# ESP-12S.net
KiCad netlist of a schematic drawn in Altium Designer
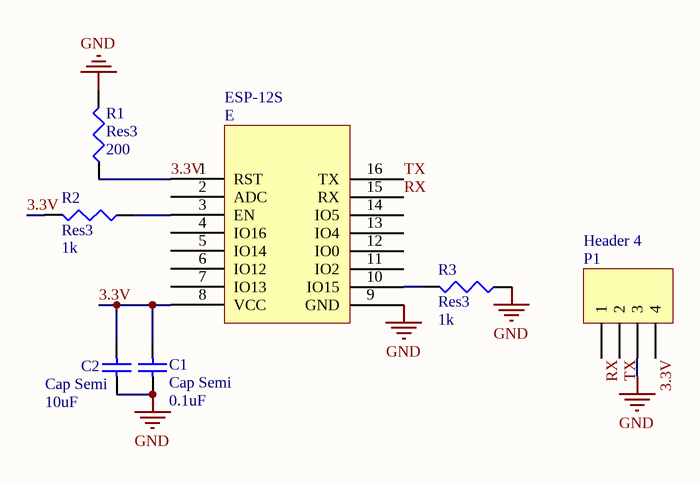
[diagram p0: ESP-12S.SchDoc]

(export (version "E")
  (design (tool "Eeschema 10.0.6"))
  (components
    (comp (ref "C1")
      (value "Cap Semi")
      (footprint "1608[0603]")
      (description "Capacitor (Semiconductor SIM Model)")
      (fields (field (name "ALTIUM_VALUE") "0.1uF") (field (name "PUBLISHER") "Altium Limited"))
      (libsource (lib "Miscellaneous Devices") (part "Cap Semi"))
    )
    (comp (ref "C2")
      (value "Cap Semi")
      (footprint "C2512")
      (description "Capacitor (Semiconductor SIM Model)")
      (fields (field (name "ALTIUM_VALUE") "10uF") (field (name "PUBLISHER") "Altium Limited"))
      (libsource (lib "Miscellaneous Devices") (part "Cap Semi"))
    )
    (comp (ref "E") (value "ESP-12S") (footprint "ESP-12S") (libsource (lib "ESP-12S") (part "ESP-12S")))
    (comp (ref "P1")
      (value "Header 4")
      (footprint "HDR1X4")
      (description "Header, 4-Pin")
      (fields (field (name "PUBLISHER") "Altium Limited"))
      (libsource (lib "Miscellaneous Connectors") (part "Header 4"))
    )
    (comp (ref "R1")
      (value "Res3")
      (footprint "J1-0603")
      (description "Resistor")
      (fields (field (name "ALTIUM_VALUE") "200") (field (name "PUBLISHER") "Altium Limited"))
      (libsource (lib "Miscellaneous Devices") (part "Res3"))
    )
    (comp (ref "R2")
      (value "Res3")
      (footprint "J1-0603")
      (description "Resistor")
      (fields (field (name "ALTIUM_VALUE") "1k") (field (name "PUBLISHER") "Altium Limited"))
      (libsource (lib "Miscellaneous Devices") (part "Res3"))
    )
    (comp (ref "R3")
      (value "Res3")
      (footprint "J1-0603")
      (description "Resistor")
      (fields (field (name "ALTIUM_VALUE") "1k") (field (name "PUBLISHER") "Altium Limited"))
      (libsource (lib "Miscellaneous Devices") (part "Res3"))
    )
  )
  (nets
    (net (code "1") (name "/3.3V") (class "Default")
      (node (ref "C1") (pin "2") (pinfunction "2_2") (pintype "passive"))
      (node (ref "C2") (pin "2") (pinfunction "2_2") (pintype "passive"))
      (node (ref "E") (pin "1") (pinfunction "RST_1") (pintype "passive"))
      (node (ref "E") (pin "8") (pinfunction "VCC_8") (pintype "passive"))
      (node (ref "P1") (pin "4") (pinfunction "4_4") (pintype "passive"))
      (node (ref "R1") (pin "1") (pinfunction "1_1") (pintype "passive"))
      (node (ref "R2") (pin "2") (pinfunction "2_2") (pintype "passive"))
    )
    (net (code "2") (name "/RX") (class "Default")
      (node (ref "E") (pin "15") (pinfunction "RX_15") (pintype "passive"))
      (node (ref "P1") (pin "1") (pinfunction "1_1") (pintype "passive"))
    )
    (net (code "3") (name "/TX") (class "Default")
      (node (ref "E") (pin "16") (pinfunction "TX_16") (pintype "passive"))
      (node (ref "P1") (pin "2") (pinfunction "2_2") (pintype "passive"))
    )
    (net (code "4") (name "GND") (class "Default")
      (node (ref "C1") (pin "1") (pinfunction "1_1") (pintype "passive"))
      (node (ref "C2") (pin "1") (pinfunction "1_1") (pintype "passive"))
      (node (ref "E") (pin "9") (pinfunction "GND_9") (pintype "passive"))
      (node (ref "P1") (pin "3") (pinfunction "3_3") (pintype "passive"))
      (node (ref "R1") (pin "2") (pinfunction "2_2") (pintype "passive"))
      (node (ref "R3") (pin "1") (pinfunction "1_1") (pintype "passive"))
    )
    (net (code "5") (name "Net-(E-EN)") (class "Default")
      (node (ref "E") (pin "3") (pinfunction "EN_3") (pintype "passive"))
      (node (ref "R2") (pin "1") (pinfunction "1_1") (pintype "passive"))
    )
    (net (code "6") (name "Net-(E-IO15)") (class "Default")
      (node (ref "E") (pin "10") (pinfunction "IO15_10") (pintype "passive"))
      (node (ref "R3") (pin "2") (pinfunction "2_2") (pintype "passive"))
    )
    (net (code "7") (name "unconnected-(E-ADC-Pad2)") (class "Default")
      (node (ref "E") (pin "2") (pinfunction "ADC_2") (pintype "passive"))
    )
    (net (code "8") (name "unconnected-(E-IO0-Pad12)") (class "Default")
      (node (ref "E") (pin "12") (pinfunction "IO0_12") (pintype "passive"))
    )
    (net (code "9") (name "unconnected-(E-IO2-Pad11)") (class "Default")
      (node (ref "E") (pin "11") (pinfunction "IO2_11") (pintype "passive"))
    )
    (net (code "10") (name "unconnected-(E-IO4-Pad13)") (class "Default")
      (node (ref "E") (pin "13") (pinfunction "IO4_13") (pintype "passive"))
    )
    (net (code "11") (name "unconnected-(E-IO5-Pad14)") (class "Default")
      (node (ref "E") (pin "14") (pinfunction "IO5_14") (pintype "passive"))
    )
    (net (code "12") (name "unconnected-(E-IO12-Pad6)") (class "Default")
      (node (ref "E") (pin "6") (pinfunction "IO12_6") (pintype "passive"))
    )
    (net (code "13") (name "unconnected-(E-IO13-Pad7)") (class "Default")
      (node (ref "E") (pin "7") (pinfunction "IO13_7") (pintype "passive"))
    )
    (net (code "14") (name "unconnected-(E-IO14-Pad5)") (class "Default")
      (node (ref "E") (pin "5") (pinfunction "IO14_5") (pintype "passive"))
    )
    (net (code "15") (name "unconnected-(E-IO16-Pad4)") (class "Default")
      (node (ref "E") (pin "4") (pinfunction "IO16_4") (pintype "passive"))
    )
  )
)
